# dirtcheaprx_nano.net
KiCad netlist of a schematic drawn in EAGLE
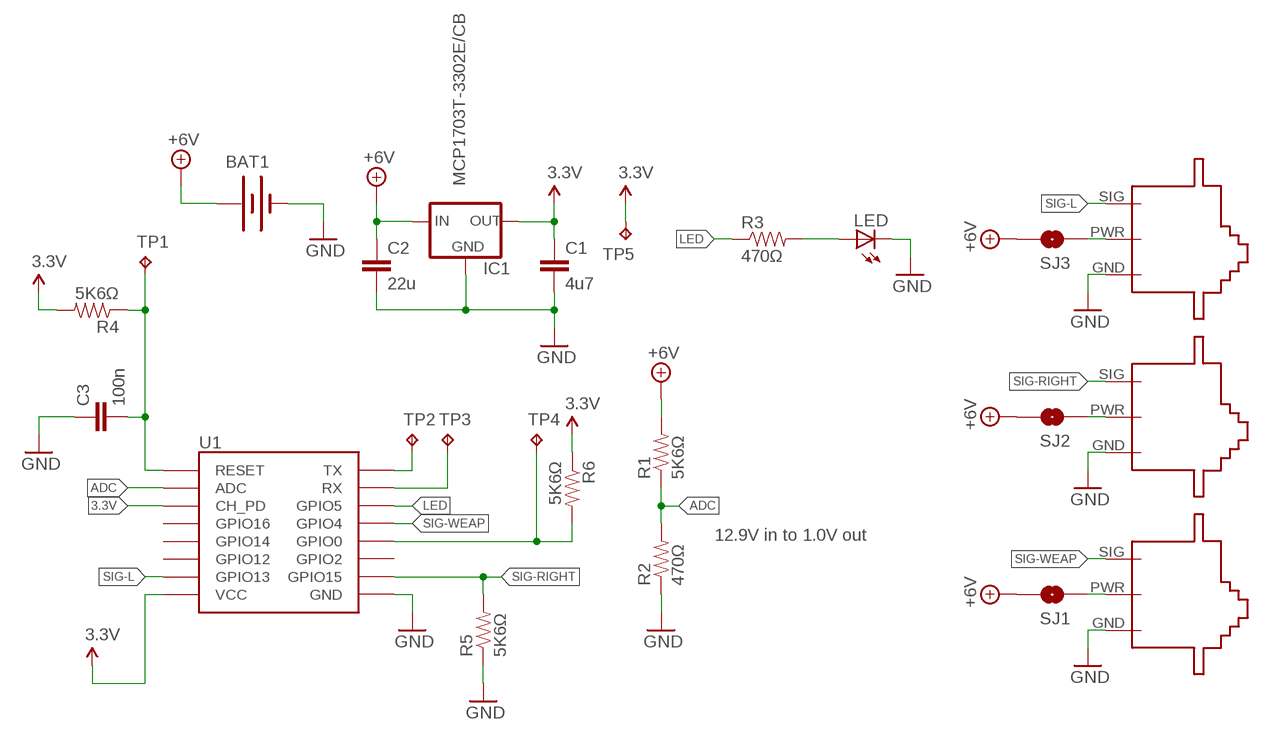
[diagram p0: schematic, sheet 1]

(export (version "E")
  (design (tool "Eeschema 10.0.6"))
  (components
    (comp (ref "BAT1")
      (value "BATTERY-WIRE-CONN")
      (footprint "eagle-import:BATT-WIRE-CONN")
      (libsource (lib "eagle-import") (part "BATTERY-WIRE-CONN"))
    )
    (comp (ref "C1")
      (value "4u7")
      (footprint "eagle-import:0805")
      (libsource (lib "eagle-import") (part "CAP0805"))
    )
    (comp (ref "C2")
      (value "22u")
      (footprint "eagle-import:0805")
      (libsource (lib "eagle-import") (part "CAP0805"))
    )
    (comp (ref "C3")
      (value "100n")
      (footprint "eagle-import:0603-CAP")
      (libsource (lib "eagle-import") (part "CAP0603-CAP"))
    )
    (comp (ref "IC1")
      (value "MCP1703T-3302E/CB")
      (footprint "eagle-import:SOT23-3")
      (libsource (lib "eagle-import") (part "V_REG_78XX-SOT"))
    )
    (comp (ref "LED")
      (value "LED5MM")
      (footprint "eagle-import:LED5MM")
      (libsource (lib "eagle-import") (part "LED5MM"))
    )
    (comp (ref "R1")
      (value "5K6Ω")
      (footprint "eagle-import:0603-RES")
      (libsource (lib "eagle-import") (part "RESISTOR0603-RES"))
    )
    (comp (ref "R2")
      (value "470Ω")
      (footprint "eagle-import:0603-RES")
      (libsource (lib "eagle-import") (part "RESISTOR0603-RES"))
    )
    (comp (ref "R3")
      (value "470Ω")
      (footprint "eagle-import:0603-RES")
      (libsource (lib "eagle-import") (part "RESISTOR0603-RES"))
    )
    (comp (ref "R4")
      (value "5K6Ω")
      (footprint "eagle-import:0603-RES")
      (libsource (lib "eagle-import") (part "RESISTOR0603-RES"))
    )
    (comp (ref "R5")
      (value "5K6Ω")
      (footprint "eagle-import:0603-RES")
      (libsource (lib "eagle-import") (part "RESISTOR0603-RES"))
    )
    (comp (ref "R6")
      (value "5K6Ω")
      (footprint "eagle-import:0603-RES")
      (libsource (lib "eagle-import") (part "RESISTOR0603-RES"))
    )
    (comp (ref "SERVO1")
      (value "SERVO-SMD-EDGE-1F")
      (footprint "eagle-import:SERVO-EDGE-F")
      (libsource (lib "eagle-import") (part "SERVO-SMD-EDGE-1F"))
    )
    (comp (ref "SERVO2")
      (value "SERVO-SMD-EDGE-1")
      (footprint "eagle-import:SERVO-EDGE")
      (libsource (lib "eagle-import") (part "SERVO-SMD-EDGE-1"))
    )
    (comp (ref "SERVO3")
      (value "SERVO-SMD-EDGE-1")
      (footprint "eagle-import:SERVO-EDGE")
      (libsource (lib "eagle-import") (part "SERVO-SMD-EDGE-1"))
    )
    (comp (ref "SJ1")
      (value "SOLDERJUMPERNO")
      (footprint "eagle-import:SJ_2S-NO")
      (libsource (lib "eagle-import") (part "SOLDERJUMPERNO"))
    )
    (comp (ref "SJ2")
      (value "SOLDERJUMPERNO")
      (footprint "eagle-import:SJ_2S-NO")
      (libsource (lib "eagle-import") (part "SOLDERJUMPERNO"))
    )
    (comp (ref "SJ3")
      (value "SOLDERJUMPERNO")
      (footprint "eagle-import:SJ_2S-NO")
      (libsource (lib "eagle-import") (part "SOLDERJUMPERNO"))
    )
    (comp (ref "TP1")
      (value "TPPAD1-13")
      (footprint "eagle-import:P1-13")
      (libsource (lib "eagle-import") (part "TPPAD1-13"))
    )
    (comp (ref "TP2")
      (value "TPPAD1-13")
      (footprint "eagle-import:P1-13")
      (libsource (lib "eagle-import") (part "TPPAD1-13"))
    )
    (comp (ref "TP3")
      (value "TPPAD1-13")
      (footprint "eagle-import:P1-13")
      (libsource (lib "eagle-import") (part "TPPAD1-13"))
    )
    (comp (ref "TP4")
      (value "TPPAD1-13")
      (footprint "eagle-import:P1-13")
      (libsource (lib "eagle-import") (part "TPPAD1-13"))
    )
    (comp (ref "TP5")
      (value "TPPAD1-13")
      (footprint "eagle-import:P1-13")
      (libsource (lib "eagle-import") (part "TPPAD1-13"))
    )
    (comp (ref "U1")
      (value "ESP12SMD")
      (footprint "eagle-import:ESP12SE-SMD")
      (libsource (lib "eagle-import") (part "ESP12SMD"))
    )
  )
  (nets
    (net (code "1") (name "+6V") (class "Default")
      (node (ref "BAT1") (pin "POS") (pinfunction "+_POS") (pintype "power_in"))
      (node (ref "C2") (pin "1") (pinfunction "1_1") (pintype "passive"))
      (node (ref "IC1") (pin "3") (pinfunction "IN_3") (pintype "input"))
      (node (ref "R1") (pin "2") (pinfunction "2_2") (pintype "passive"))
      (node (ref "SJ1") (pin "2") (pinfunction "2_2") (pintype "passive"))
      (node (ref "SJ2") (pin "2") (pinfunction "2_2") (pintype "passive"))
      (node (ref "SJ3") (pin "2") (pinfunction "2_2") (pintype "passive"))
    )
    (net (code "2") (name "3.3V") (class "Default")
      (node (ref "C1") (pin "1") (pinfunction "1_1") (pintype "passive"))
      (node (ref "IC1") (pin "2") (pinfunction "OUT_2") (pintype "output"))
      (node (ref "R4") (pin "2") (pinfunction "2_2") (pintype "passive"))
      (node (ref "R6") (pin "1") (pinfunction "1_1") (pintype "passive"))
      (node (ref "TP5") (pin "TP") (pinfunction "TP_TP") (pintype "input"))
      (node (ref "U1") (pin "CH_PD") (pinfunction "CH_PD_CH_PD") (pintype "bidirectional"))
      (node (ref "U1") (pin "VCC") (pinfunction "VCC_VCC") (pintype "bidirectional"))
    )
    (net (code "3") (name "ADC") (class "Default")
      (node (ref "R1") (pin "1") (pinfunction "1_1") (pintype "passive"))
      (node (ref "R2") (pin "2") (pinfunction "2_2") (pintype "passive"))
      (node (ref "U1") (pin "ADC") (pinfunction "ADC_ADC") (pintype "bidirectional"))
    )
    (net (code "4") (name "GND") (class "Default")
      (node (ref "BAT1") (pin "NEG") (pinfunction "-_NEG") (pintype "power_in"))
      (node (ref "C1") (pin "2") (pinfunction "2_2") (pintype "passive"))
      (node (ref "C2") (pin "2") (pinfunction "2_2") (pintype "passive"))
      (node (ref "C3") (pin "1") (pinfunction "1_1") (pintype "passive"))
      (node (ref "IC1") (pin "1") (pinfunction "GND_1") (pintype "input"))
      (node (ref "LED") (pin "K") (pinfunction "C_K") (pintype "passive"))
      (node (ref "R2") (pin "1") (pinfunction "1_1") (pintype "passive"))
      (node (ref "R5") (pin "1") (pinfunction "1_1") (pintype "passive"))
      (node (ref "SERVO1") (pin "GND") (pinfunction "GND_GND") (pintype "bidirectional"))
      (node (ref "SERVO2") (pin "GND") (pinfunction "GND_GND") (pintype "bidirectional"))
      (node (ref "SERVO3") (pin "GND") (pinfunction "GND_GND") (pintype "bidirectional"))
      (node (ref "U1") (pin "GND") (pinfunction "GND_GND") (pintype "bidirectional"))
    )
    (net (code "5") (name "LED") (class "Default")
      (node (ref "R3") (pin "1") (pinfunction "1_1") (pintype "passive"))
      (node (ref "U1") (pin "GPIO5") (pinfunction "GPIO5_GPIO5") (pintype "bidirectional"))
    )
    (net (code "6") (name "Net-(C3-Pad2)") (class "Default")
      (node (ref "C3") (pin "2") (pinfunction "2_2") (pintype "passive"))
      (node (ref "R4") (pin "1") (pinfunction "1_1") (pintype "passive"))
      (node (ref "TP1") (pin "TP") (pinfunction "TP_TP") (pintype "input"))
      (node (ref "U1") (pin "RESET") (pinfunction "RESET_RESET") (pintype "bidirectional"))
    )
    (net (code "7") (name "Net-(LED-PadA)") (class "Default")
      (node (ref "LED") (pin "A") (pinfunction "A_A") (pintype "passive"))
      (node (ref "R3") (pin "2") (pinfunction "2_2") (pintype "passive"))
    )
    (net (code "8") (name "Net-(R6-Pad2)") (class "Default")
      (node (ref "R6") (pin "2") (pinfunction "2_2") (pintype "passive"))
      (node (ref "TP4") (pin "TP") (pinfunction "TP_TP") (pintype "input"))
      (node (ref "U1") (pin "GPIO0") (pinfunction "GPIO0_GPIO0") (pintype "bidirectional"))
    )
    (net (code "9") (name "Net-(SERVO1-PadPWR)") (class "Default")
      (node (ref "SERVO1") (pin "PWR") (pinfunction "PWR_PWR") (pintype "bidirectional"))
      (node (ref "SJ1") (pin "1") (pinfunction "1_1") (pintype "passive"))
    )
    (net (code "10") (name "Net-(SERVO2-PadPWR)") (class "Default")
      (node (ref "SERVO2") (pin "PWR") (pinfunction "PWR_PWR") (pintype "bidirectional"))
      (node (ref "SJ2") (pin "1") (pinfunction "1_1") (pintype "passive"))
    )
    (net (code "11") (name "Net-(SERVO3-PadPWR)") (class "Default")
      (node (ref "SERVO3") (pin "PWR") (pinfunction "PWR_PWR") (pintype "bidirectional"))
      (node (ref "SJ3") (pin "1") (pinfunction "1_1") (pintype "passive"))
    )
    (net (code "12") (name "Net-(U1-RX)") (class "Default")
      (node (ref "TP3") (pin "TP") (pinfunction "TP_TP") (pintype "input"))
      (node (ref "U1") (pin "RXD0") (pinfunction "RX_RXD0") (pintype "bidirectional"))
    )
    (net (code "13") (name "Net-(U1-TX)") (class "Default")
      (node (ref "TP2") (pin "TP") (pinfunction "TP_TP") (pintype "input"))
      (node (ref "U1") (pin "TXD0") (pinfunction "TX_TXD0") (pintype "bidirectional"))
    )
    (net (code "14") (name "SIG-L") (class "Default")
      (node (ref "SERVO3") (pin "SIG") (pinfunction "SIG_SIG") (pintype "bidirectional"))
      (node (ref "U1") (pin "GPIO13") (pinfunction "GPIO13_GPIO13") (pintype "bidirectional"))
    )
    (net (code "15") (name "SIG-RIGHT") (class "Default")
      (node (ref "R5") (pin "2") (pinfunction "2_2") (pintype "passive"))
      (node (ref "SERVO2") (pin "SIG") (pinfunction "SIG_SIG") (pintype "bidirectional"))
      (node (ref "U1") (pin "GPIO15") (pinfunction "GPIO15_GPIO15") (pintype "bidirectional"))
    )
    (net (code "16") (name "SIG-WEAP") (class "Default")
      (node (ref "SERVO1") (pin "SIG") (pinfunction "SIG_SIG") (pintype "bidirectional"))
      (node (ref "U1") (pin "GPIO4") (pinfunction "GPIO4_GPIO4") (pintype "bidirectional"))
    )
    (net (code "17") (name "unconnected-(U1-PadGPIO2)") (class "Default")
      (node (ref "U1") (pin "GPIO2") (pinfunction "GPIO2_GPIO2") (pintype "bidirectional"))
    )
    (net (code "18") (name "unconnected-(U1-PadGPIO12)") (class "Default")
      (node (ref "U1") (pin "GPIO12") (pinfunction "GPIO12_GPIO12") (pintype "bidirectional"))
    )
    (net (code "19") (name "unconnected-(U1-PadGPIO14)") (class "Default")
      (node (ref "U1") (pin "GPIO14") (pinfunction "GPIO14_GPIO14") (pintype "bidirectional"))
    )
    (net (code "20") (name "unconnected-(U1-PadGPIO16)") (class "Default")
      (node (ref "U1") (pin "GPIO16") (pinfunction "GPIO16_GPIO16") (pintype "bidirectional"))
    )
  )
)
